# ADAPTER_WOLF.net
KiCad netlist of a schematic drawn in Altium Designer
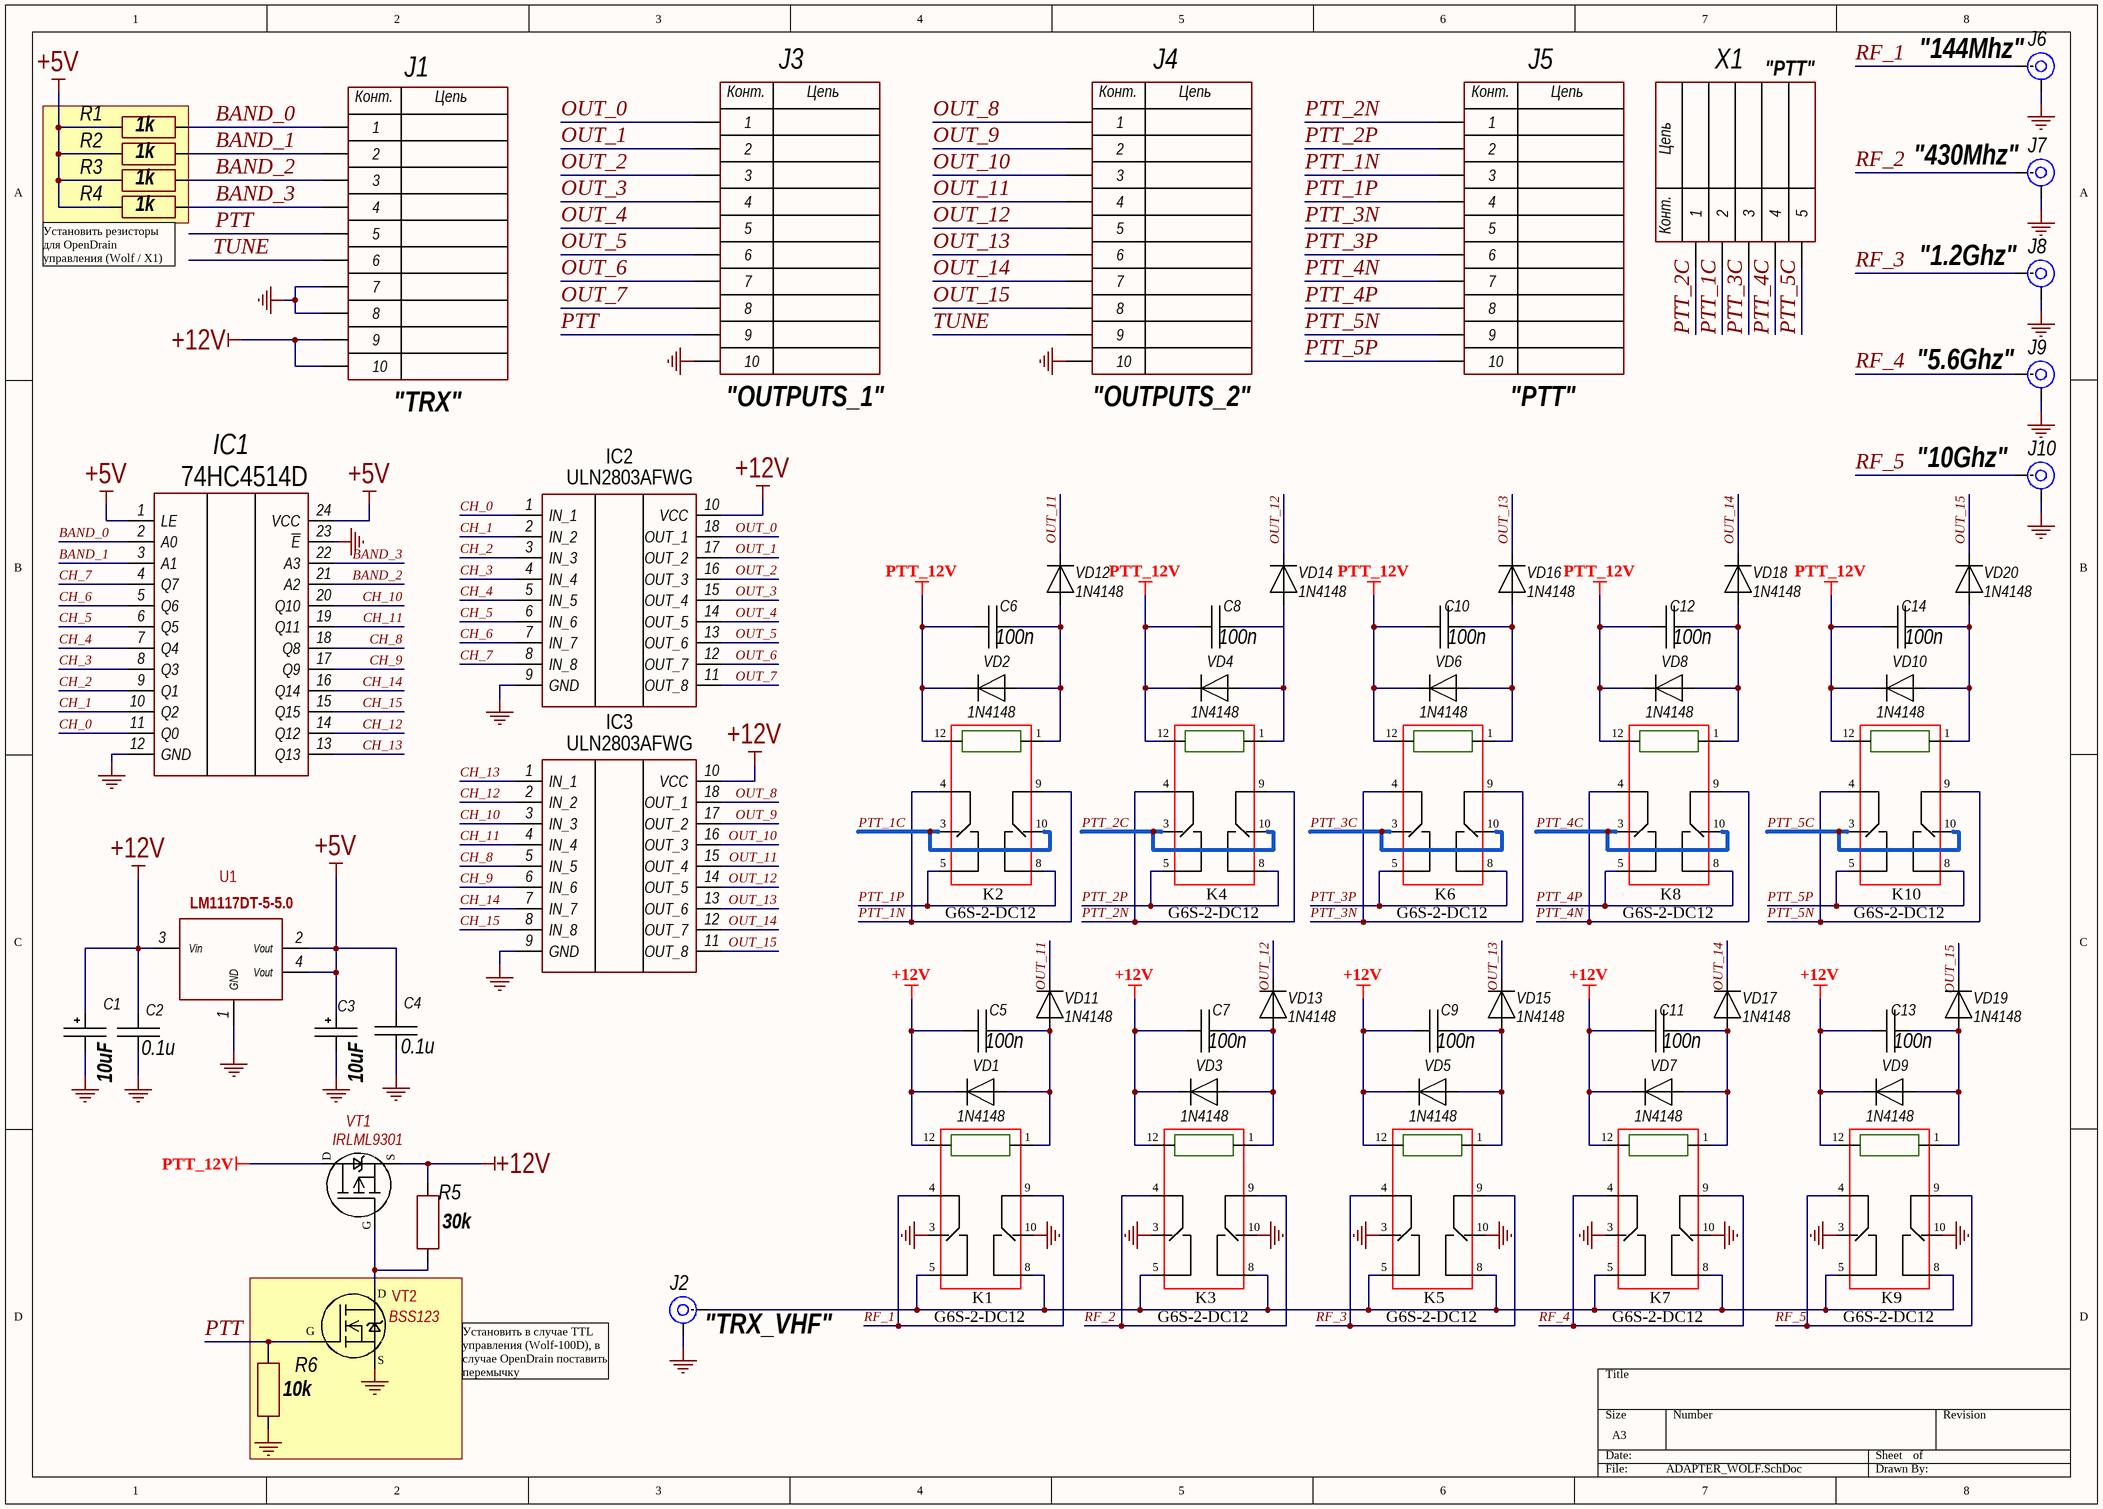
[diagram p0: ADAPTER_WOLF.SchDoc]

(export (version "E")
  (design (tool "Eeschema 10.0.6"))
  (components
    (comp (ref "C1")
      (value "10uF")
      (footprint "standard:TANTAL_B")
      (libsource (lib "Discrete") (part "TantalCap"))
    )
    (comp (ref "C2")
      (value "0.1u")
      (footprint "standard:CH0805C")
      (libsource (lib "Discrete") (part "Capacitor"))
    )
    (comp (ref "C3")
      (value "10uF")
      (footprint "standard:TANTAL_B")
      (libsource (lib "Discrete") (part "TantalCap"))
    )
    (comp (ref "C4")
      (value "0.1u")
      (footprint "standard:CH0805C")
      (libsource (lib "Discrete") (part "Capacitor"))
    )
    (comp (ref "C5")
      (value "100n")
      (footprint "standard:CH0805C")
      (libsource (lib "Discrete") (part "Capacitor"))
    )
    (comp (ref "C6")
      (value "100n")
      (footprint "standard:CH0805C")
      (libsource (lib "Discrete") (part "Capacitor"))
    )
    (comp (ref "C7")
      (value "100n")
      (footprint "standard:CH0805C")
      (libsource (lib "Discrete") (part "Capacitor"))
    )
    (comp (ref "C8")
      (value "100n")
      (footprint "standard:CH0805C")
      (libsource (lib "Discrete") (part "Capacitor"))
    )
    (comp (ref "C9")
      (value "100n")
      (footprint "standard:CH0805C")
      (libsource (lib "Discrete") (part "Capacitor"))
    )
    (comp (ref "C10")
      (value "100n")
      (footprint "standard:CH0805C")
      (libsource (lib "Discrete") (part "Capacitor"))
    )
    (comp (ref "C11")
      (value "100n")
      (footprint "standard:CH0805C")
      (libsource (lib "Discrete") (part "Capacitor"))
    )
    (comp (ref "C12")
      (value "100n")
      (footprint "standard:CH0805C")
      (libsource (lib "Discrete") (part "Capacitor"))
    )
    (comp (ref "C13")
      (value "100n")
      (footprint "standard:CH0805C")
      (libsource (lib "Discrete") (part "Capacitor"))
    )
    (comp (ref "C14")
      (value "100n")
      (footprint "standard:CH0805C")
      (libsource (lib "Discrete") (part "Capacitor"))
    )
    (comp (ref "IC1")
      (value "74HC4514D")
      (footprint "24-SOIC (W)")
      (libsource (lib "Digital") (part "74HC4514D"))
    )
    (comp (ref "IC2")
      (value "ULN2803AFWG")
      (footprint "18-SOIC (W)")
      (libsource (lib "Digital") (part "ULN2803AFWG"))
    )
    (comp (ref "IC3")
      (value "ULN2803AFWG")
      (footprint "18-SOIC (W)")
      (libsource (lib "Digital") (part "ULN2803AFWG"))
    )
    (comp (ref "J1")
      (value "\"TRX\"")
      (footprint "custom:CON: PLD-10")
      (libsource (lib "Connectors") (part "10-Connector"))
    )
    (comp (ref "J2")
      (value "\"TRX_VHF\"")
      (footprint "custom:CON: SMA")
      (description "RF")
      (libsource (lib "Connectors") (part "SMA"))
    )
    (comp (ref "J3")
      (value "\"OUTPUTS_1\"")
      (footprint "custom:CON: PLD-10")
      (libsource (lib "Connectors") (part "10-Connector"))
    )
    (comp (ref "J4")
      (value "\"OUTPUTS_2\"")
      (footprint "custom:CON: PLD-10")
      (libsource (lib "Connectors") (part "10-Connector"))
    )
    (comp (ref "J5")
      (value "\"PTT\"")
      (footprint "custom:CON: PLD-10")
      (libsource (lib "Connectors") (part "10-Connector"))
    )
    (comp (ref "J6")
      (value "\"144Mhz\"")
      (footprint "custom:CON: SMA")
      (description "RF")
      (libsource (lib "Connectors") (part "SMA"))
    )
    (comp (ref "J7")
      (value "\"430Mhz\"")
      (footprint "custom:CON: SMA")
      (description "RF")
      (libsource (lib "Connectors") (part "SMA"))
    )
    (comp (ref "J8")
      (value "\"1.2Ghz\"")
      (footprint "custom:CON: SMA")
      (description "RF")
      (libsource (lib "Connectors") (part "SMA"))
    )
    (comp (ref "J9")
      (value "\"5.6Ghz\"")
      (footprint "custom:CON: SMA")
      (description "RF")
      (libsource (lib "Connectors") (part "SMA"))
    )
    (comp (ref "J10")
      (value "\"10Ghz\"")
      (footprint "custom:CON: SMA")
      (description "RF")
      (libsource (lib "Connectors") (part "SMA"))
    )
    (comp (ref "K1")
      (value "G6S-2-DС12")
      (footprint "G6S-2-DC12")
      (libsource (lib "Relay") (part "G6S-2_TRS"))
    )
    (comp (ref "K2")
      (value "G6S-2-DС12")
      (footprint "G6S-2-DC12")
      (libsource (lib "Relay") (part "G6S-2_TRS"))
    )
    (comp (ref "K3")
      (value "G6S-2-DС12")
      (footprint "G6S-2-DC12")
      (libsource (lib "Relay") (part "G6S-2_TRS"))
    )
    (comp (ref "K4")
      (value "G6S-2-DС12")
      (footprint "G6S-2-DC12")
      (libsource (lib "Relay") (part "G6S-2_TRS"))
    )
    (comp (ref "K5") (value "G6S-2-DС12") (footprint "G6S-2-DC12") (libsource (lib "") (part "G6S-2_TRS_1")))
    (comp (ref "K6") (value "G6S-2-DС12") (footprint "G6S-2-DC12") (libsource (lib "") (part "G6S-2_TRS_2")))
    (comp (ref "K7")
      (value "G6S-2-DС12")
      (footprint "G6S-2-DC12")
      (libsource (lib "Relay") (part "G6S-2_TRS"))
    )
    (comp (ref "K8")
      (value "G6S-2-DС12")
      (footprint "G6S-2-DC12")
      (libsource (lib "Relay") (part "G6S-2_TRS"))
    )
    (comp (ref "K9")
      (value "G6S-2-DС12")
      (footprint "G6S-2-DC12")
      (libsource (lib "Relay") (part "G6S-2_TRS"))
    )
    (comp (ref "K10")
      (value "G6S-2-DС12")
      (footprint "G6S-2-DC12")
      (libsource (lib "Relay") (part "G6S-2_TRS"))
    )
    (comp (ref "R1")
      (value "1k")
      (footprint "standard:CH0805R")
      (libsource (lib "Discrete") (part "Resistor"))
    )
    (comp (ref "R2")
      (value "1k")
      (footprint "standard:CH0805R")
      (libsource (lib "Discrete") (part "Resistor"))
    )
    (comp (ref "R3") (value "1k") (footprint "standard:CH0805R") (libsource (lib "") (part "Resistor_2")))
    (comp (ref "R4")
      (value "1k")
      (footprint "standard:CH0805R")
      (libsource (lib "Discrete") (part "Resistor"))
    )
    (comp (ref "R5") (value "30k") (footprint "standard:CH0805R") (libsource (lib "") (part "Resistor_1")))
    (comp (ref "R6") (value "10k") (footprint "standard:CH0805R") (libsource (lib "") (part "Resistor_1")))
    (comp (ref "U1") (value "LM1117DT-5-5.0") (footprint "SOT223") (libsource (lib "Analog") (part "AMS117")))
    (comp (ref "VD1") (value "1N4148") (footprint "1N4148") (libsource (lib "Diods") (part "Diod")))
    (comp (ref "VD2") (value "1N4148") (footprint "1N4148") (libsource (lib "Diods") (part "Diod")))
    (comp (ref "VD3") (value "1N4148") (footprint "1N4148") (libsource (lib "Diods") (part "Diod")))
    (comp (ref "VD4") (value "1N4148") (footprint "1N4148") (libsource (lib "Diods") (part "Diod")))
    (comp (ref "VD5") (value "1N4148") (footprint "1N4148") (libsource (lib "Diods") (part "Diod")))
    (comp (ref "VD6") (value "1N4148") (footprint "1N4148") (libsource (lib "Diods") (part "Diod")))
    (comp (ref "VD7") (value "1N4148") (footprint "1N4148") (libsource (lib "Diods") (part "Diod")))
    (comp (ref "VD8") (value "1N4148") (footprint "1N4148") (libsource (lib "Diods") (part "Diod")))
    (comp (ref "VD9") (value "1N4148") (footprint "1N4148") (libsource (lib "Diods") (part "Diod")))
    (comp (ref "VD10") (value "1N4148") (footprint "1N4148") (libsource (lib "Diods") (part "Diod")))
    (comp (ref "VD11") (value "1N4148") (footprint "1N4148") (libsource (lib "Diods") (part "Diod")))
    (comp (ref "VD12") (value "1N4148") (footprint "1N4148") (libsource (lib "Diods") (part "Diod")))
    (comp (ref "VD13") (value "1N4148") (footprint "1N4148") (libsource (lib "Diods") (part "Diod")))
    (comp (ref "VD14") (value "1N4148") (footprint "1N4148") (libsource (lib "Diods") (part "Diod")))
    (comp (ref "VD15") (value "1N4148") (footprint "1N4148") (libsource (lib "Diods") (part "Diod")))
    (comp (ref "VD16") (value "1N4148") (footprint "1N4148") (libsource (lib "Diods") (part "Diod")))
    (comp (ref "VD17") (value "1N4148") (footprint "1N4148") (libsource (lib "Diods") (part "Diod")))
    (comp (ref "VD18") (value "1N4148") (footprint "1N4148") (libsource (lib "Diods") (part "Diod")))
    (comp (ref "VD19") (value "1N4148") (footprint "1N4148") (libsource (lib "Diods") (part "Diod")))
    (comp (ref "VD20") (value "1N4148") (footprint "1N4148") (libsource (lib "Diods") (part "Diod")))
    (comp (ref "VT1")
      (value "IRLML9301")
      (footprint "SOT23_132")
      (libsource (lib "Transistor") (part "P-KANAL"))
    )
    (comp (ref "VT2")
      (value "BSS123")
      (footprint "SOT23_132")
      (libsource (lib "Transistor") (part "N-KANAL"))
    )
    (comp (ref "X1")
      (value "\"PTT\"")
      (footprint "custom:CON: PLS-5")
      (libsource (lib "Connectors") (part "5-Connector"))
    )
  )
  (nets
    (net (code "1") (name "+5V") (class "Default")
      (node (ref "C3") (pin "1") (pinfunction "1_1") (pintype "power_in"))
      (node (ref "C4") (pin "2") (pinfunction "2_2") (pintype "power_in"))
      (node (ref "IC1") (pin "1") (pinfunction "LE_1") (pintype "passive"))
      (node (ref "IC1") (pin "24") (pinfunction "VCC_24") (pintype "passive"))
      (node (ref "R1") (pin "1") (pinfunction "1_1") (pintype "passive"))
      (node (ref "R2") (pin "1") (pinfunction "1_1") (pintype "passive"))
      (node (ref "R3") (pin "1") (pinfunction "1_1") (pintype "passive"))
      (node (ref "R4") (pin "1") (pinfunction "1_1") (pintype "passive"))
      (node (ref "U1") (pin "2") (pinfunction "Vout_2") (pintype "passive"))
      (node (ref "U1") (pin "4") (pinfunction "Vout_4") (pintype "passive"))
    )
    (net (code "2") (name "+12V") (class "Default")
      (node (ref "C1") (pin "1") (pinfunction "1_1") (pintype "power_in"))
      (node (ref "C11") (pin "1") (pinfunction "1_1") (pintype "power_in"))
      (node (ref "C13") (pin "1") (pinfunction "1_1") (pintype "power_in"))
      (node (ref "C2") (pin "2") (pinfunction "2_2") (pintype "power_in"))
      (node (ref "C5") (pin "1") (pinfunction "1_1") (pintype "power_in"))
      (node (ref "C7") (pin "1") (pinfunction "1_1") (pintype "power_in"))
      (node (ref "C9") (pin "1") (pinfunction "1_1") (pintype "power_in"))
      (node (ref "IC2") (pin "10") (pinfunction "VCC_10") (pintype "passive"))
      (node (ref "IC3") (pin "10") (pinfunction "VCC_10") (pintype "passive"))
      (node (ref "J1") (pin "10") (pinfunction "10_10") (pintype "power_in"))
      (node (ref "J1") (pin "9") (pinfunction "9_9") (pintype "power_in"))
      (node (ref "K1") (pin "12") (pinfunction "12_12") (pintype "passive"))
      (node (ref "K3") (pin "12") (pinfunction "12_12") (pintype "passive"))
      (node (ref "K5") (pin "12") (pinfunction "2_12") (pintype "passive"))
      (node (ref "K7") (pin "12") (pinfunction "12_12") (pintype "passive"))
      (node (ref "K9") (pin "12") (pinfunction "12_12") (pintype "passive"))
      (node (ref "R5") (pin "2") (pinfunction "2_2") (pintype "passive"))
      (node (ref "U1") (pin "3") (pinfunction "Vin_3") (pintype "passive"))
      (node (ref "VD1") (pin "2") (pinfunction "2_2") (pintype "passive"))
      (node (ref "VD3") (pin "2") (pinfunction "2_2") (pintype "passive"))
      (node (ref "VD5") (pin "2") (pinfunction "2_2") (pintype "passive"))
      (node (ref "VD7") (pin "2") (pinfunction "2_2") (pintype "passive"))
      (node (ref "VD9") (pin "2") (pinfunction "2_2") (pintype "passive"))
      (node (ref "VT1") (pin "2") (pinfunction "Исток_2") (pintype "passive"))
    )
    (net (code "3") (name "/BAND_0") (class "Default")
      (node (ref "IC1") (pin "2") (pinfunction "A0_2") (pintype "passive"))
      (node (ref "J1") (pin "1") (pinfunction "1_1") (pintype "passive"))
      (node (ref "R1") (pin "2") (pinfunction "2_2") (pintype "passive"))
    )
    (net (code "4") (name "/BAND_1") (class "Default")
      (node (ref "IC1") (pin "3") (pinfunction "A1_3") (pintype "passive"))
      (node (ref "J1") (pin "2") (pinfunction "2_2") (pintype "passive"))
      (node (ref "R2") (pin "2") (pinfunction "2_2") (pintype "passive"))
    )
    (net (code "5") (name "/BAND_2") (class "Default")
      (node (ref "IC1") (pin "21") (pinfunction "A2_21") (pintype "passive"))
      (node (ref "J1") (pin "3") (pinfunction "3_3") (pintype "power_in"))
      (node (ref "R3") (pin "2") (pinfunction "2_2") (pintype "passive"))
    )
    (net (code "6") (name "/BAND_3") (class "Default")
      (node (ref "IC1") (pin "22") (pinfunction "A3_22") (pintype "passive"))
      (node (ref "J1") (pin "4") (pinfunction "4_4") (pintype "power_in"))
      (node (ref "R4") (pin "2") (pinfunction "2_2") (pintype "passive"))
    )
    (net (code "7") (name "/CH_0") (class "Default")
      (node (ref "IC1") (pin "11") (pinfunction "Q0_11") (pintype "passive"))
      (node (ref "IC2") (pin "1") (pinfunction "IN_1_1") (pintype "passive"))
    )
    (net (code "8") (name "/CH_1") (class "Default")
      (node (ref "IC1") (pin "10") (pinfunction "Q2_10") (pintype "passive"))
      (node (ref "IC2") (pin "2") (pinfunction "IN_2_2") (pintype "passive"))
    )
    (net (code "9") (name "/CH_2") (class "Default")
      (node (ref "IC1") (pin "9") (pinfunction "Q1_9") (pintype "passive"))
      (node (ref "IC2") (pin "3") (pinfunction "IN_3_3") (pintype "passive"))
    )
    (net (code "10") (name "/CH_3") (class "Default")
      (node (ref "IC1") (pin "8") (pinfunction "Q3_8") (pintype "passive"))
      (node (ref "IC2") (pin "4") (pinfunction "IN_4_4") (pintype "passive"))
    )
    (net (code "11") (name "/CH_4") (class "Default")
      (node (ref "IC1") (pin "7") (pinfunction "Q4_7") (pintype "passive"))
      (node (ref "IC2") (pin "5") (pinfunction "IN_5_5") (pintype "passive"))
    )
    (net (code "12") (name "/CH_5") (class "Default")
      (node (ref "IC1") (pin "6") (pinfunction "Q5_6") (pintype "passive"))
      (node (ref "IC2") (pin "6") (pinfunction "IN_6_6") (pintype "passive"))
    )
    (net (code "13") (name "/CH_6") (class "Default")
      (node (ref "IC1") (pin "5") (pinfunction "Q6_5") (pintype "passive"))
      (node (ref "IC2") (pin "7") (pinfunction "IN_7_7") (pintype "passive"))
    )
    (net (code "14") (name "/CH_7") (class "Default")
      (node (ref "IC1") (pin "4") (pinfunction "Q7_4") (pintype "passive"))
      (node (ref "IC2") (pin "8") (pinfunction "IN_8_8") (pintype "passive"))
    )
    (net (code "15") (name "/CH_8") (class "Default")
      (node (ref "IC1") (pin "18") (pinfunction "Q8_18") (pintype "passive"))
      (node (ref "IC3") (pin "5") (pinfunction "IN_5_5") (pintype "passive"))
    )
    (net (code "16") (name "/CH_9") (class "Default")
      (node (ref "IC1") (pin "17") (pinfunction "Q9_17") (pintype "passive"))
      (node (ref "IC3") (pin "6") (pinfunction "IN_6_6") (pintype "passive"))
    )
    (net (code "17") (name "/CH_10") (class "Default")
      (node (ref "IC1") (pin "20") (pinfunction "Q10_20") (pintype "passive"))
      (node (ref "IC3") (pin "3") (pinfunction "IN_3_3") (pintype "passive"))
    )
    (net (code "18") (name "/CH_11") (class "Default")
      (node (ref "IC1") (pin "19") (pinfunction "Q11_19") (pintype "passive"))
      (node (ref "IC3") (pin "4") (pinfunction "IN_4_4") (pintype "passive"))
    )
    (net (code "19") (name "/CH_12") (class "Default")
      (node (ref "IC1") (pin "14") (pinfunction "Q12_14") (pintype "passive"))
      (node (ref "IC3") (pin "2") (pinfunction "IN_2_2") (pintype "passive"))
    )
    (net (code "20") (name "/CH_13") (class "Default")
      (node (ref "IC1") (pin "13") (pinfunction "Q13_13") (pintype "passive"))
      (node (ref "IC3") (pin "1") (pinfunction "IN_1_1") (pintype "passive"))
    )
    (net (code "21") (name "/CH_14") (class "Default")
      (node (ref "IC1") (pin "16") (pinfunction "Q14_16") (pintype "passive"))
      (node (ref "IC3") (pin "7") (pinfunction "IN_7_7") (pintype "passive"))
    )
    (net (code "22") (name "/CH_15") (class "Default")
      (node (ref "IC1") (pin "15") (pinfunction "Q15_15") (pintype "passive"))
      (node (ref "IC3") (pin "8") (pinfunction "IN_8_8") (pintype "passive"))
    )
    (net (code "23") (name "/OUT_0") (class "Default")
      (node (ref "IC2") (pin "18") (pinfunction "OUT_1_18") (pintype "passive"))
      (node (ref "J3") (pin "1") (pinfunction "1_1") (pintype "passive"))
    )
    (net (code "24") (name "/OUT_1") (class "Default")
      (node (ref "IC2") (pin "17") (pinfunction "OUT_2_17") (pintype "passive"))
      (node (ref "J3") (pin "2") (pinfunction "2_2") (pintype "passive"))
    )
    (net (code "25") (name "/OUT_2") (class "Default")
      (node (ref "IC2") (pin "16") (pinfunction "OUT_3_16") (pintype "passive"))
      (node (ref "J3") (pin "3") (pinfunction "3_3") (pintype "power_in"))
    )
    (net (code "26") (name "/OUT_3") (class "Default")
      (node (ref "IC2") (pin "15") (pinfunction "OUT_4_15") (pintype "passive"))
      (node (ref "J3") (pin "4") (pinfunction "4_4") (pintype "power_in"))
    )
    (net (code "27") (name "/OUT_4") (class "Default")
      (node (ref "IC2") (pin "14") (pinfunction "OUT_5_14") (pintype "passive"))
      (node (ref "J3") (pin "5") (pinfunction "5_5") (pintype "power_in"))
    )
    (net (code "28") (name "/OUT_5") (class "Default")
      (node (ref "IC2") (pin "13") (pinfunction "OUT_6_13") (pintype "passive"))
      (node (ref "J3") (pin "6") (pinfunction "6_6") (pintype "power_in"))
    )
    (net (code "29") (name "/OUT_6") (class "Default")
      (node (ref "IC2") (pin "12") (pinfunction "OUT_7_12") (pintype "passive"))
      (node (ref "J3") (pin "7") (pinfunction "7_7") (pintype "power_in"))
    )
    (net (code "30") (name "/OUT_7") (class "Default")
      (node (ref "IC2") (pin "11") (pinfunction "OUT_8_11") (pintype "passive"))
      (node (ref "J3") (pin "8") (pinfunction "8_8") (pintype "power_in"))
    )
    (net (code "31") (name "/OUT_8") (class "Default")
      (node (ref "IC3") (pin "18") (pinfunction "OUT_1_18") (pintype "passive"))
      (node (ref "J4") (pin "1") (pinfunction "1_1") (pintype "passive"))
    )
    (net (code "32") (name "/OUT_9") (class "Default")
      (node (ref "IC3") (pin "17") (pinfunction "OUT_2_17") (pintype "passive"))
      (node (ref "J4") (pin "2") (pinfunction "2_2") (pintype "passive"))
    )
    (net (code "33") (name "/OUT_10") (class "Default")
      (node (ref "IC3") (pin "16") (pinfunction "OUT_3_16") (pintype "passive"))
      (node (ref "J4") (pin "3") (pinfunction "3_3") (pintype "power_in"))
    )
    (net (code "34") (name "/OUT_11") (class "Default")
      (node (ref "IC3") (pin "15") (pinfunction "OUT_4_15") (pintype "passive"))
      (node (ref "J4") (pin "4") (pinfunction "4_4") (pintype "power_in"))
      (node (ref "VD11") (pin "2") (pinfunction "2_2") (pintype "passive"))
      (node (ref "VD12") (pin "2") (pinfunction "2_2") (pintype "passive"))
    )
    (net (code "35") (name "/OUT_12") (class "Default")
      (node (ref "IC3") (pin "14") (pinfunction "OUT_5_14") (pintype "passive"))
      (node (ref "J4") (pin "5") (pinfunction "5_5") (pintype "power_in"))
      (node (ref "VD13") (pin "2") (pinfunction "2_2") (pintype "passive"))
      (node (ref "VD14") (pin "2") (pinfunction "2_2") (pintype "passive"))
    )
    (net (code "36") (name "/OUT_13") (class "Default")
      (node (ref "IC3") (pin "13") (pinfunction "OUT_6_13") (pintype "passive"))
      (node (ref "J4") (pin "6") (pinfunction "6_6") (pintype "power_in"))
      (node (ref "VD15") (pin "2") (pinfunction "2_2") (pintype "passive"))
      (node (ref "VD16") (pin "2") (pinfunction "2_2") (pintype "passive"))
    )
    (net (code "37") (name "/OUT_14") (class "Default")
      (node (ref "IC3") (pin "12") (pinfunction "OUT_7_12") (pintype "passive"))
      (node (ref "J4") (pin "7") (pinfunction "7_7") (pintype "power_in"))
      (node (ref "VD17") (pin "2") (pinfunction "2_2") (pintype "passive"))
      (node (ref "VD18") (pin "2") (pinfunction "2_2") (pintype "passive"))
    )
    (net (code "38") (name "/OUT_15") (class "Default")
      (node (ref "IC3") (pin "11") (pinfunction "OUT_8_11") (pintype "passive"))
      (node (ref "J4") (pin "8") (pinfunction "8_8") (pintype "power_in"))
      (node (ref "VD19") (pin "2") (pinfunction "2_2") (pintype "passive"))
      (node (ref "VD20") (pin "2") (pinfunction "2_2") (pintype "passive"))
    )
    (net (code "39") (name "/PTT") (class "Default")
      (node (ref "J1") (pin "5") (pinfunction "5_5") (pintype "power_in"))
      (node (ref "J3") (pin "9") (pinfunction "9_9") (pintype "power_in"))
      (node (ref "R6") (pin "2") (pinfunction "2_2") (pintype "passive"))
      (node (ref "VT2") (pin "1") (pinfunction "Затвор_1") (pintype "passive"))
    )
    (net (code "40") (name "/PTT_1N") (class "Default")
      (node (ref "J5") (pin "3") (pinfunction "3_3") (pintype "power_in"))
      (node (ref "K2") (pin "4") (pinfunction "4_4") (pintype "passive"))
      (node (ref "K2") (pin "9") (pinfunction "9_9") (pintype "passive"))
    )
    (net (code "41") (name "/PTT_1P") (class "Default")
      (node (ref "J5") (pin "4") (pinfunction "4_4") (pintype "power_in"))
      (node (ref "K2") (pin "5") (pinfunction "5_5") (pintype "passive"))
      (node (ref "K2") (pin "8") (pinfunction "8_8") (pintype "passive"))
    )
    (net (code "42") (name "/PTT_1С") (class "Default")
      (node (ref "K2") (pin "10") (pinfunction "10_10") (pintype "passive"))
      (node (ref "K2") (pin "3") (pinfunction "3_3") (pintype "passive"))
      (node (ref "X1") (pin "2") (pinfunction "2_2") (pintype "passive"))
    )
    (net (code "43") (name "/PTT_2N") (class "Default")
      (node (ref "J5") (pin "1") (pinfunction "1_1") (pintype "passive"))
      (node (ref "K4") (pin "4") (pinfunction "4_4") (pintype "passive"))
      (node (ref "K4") (pin "9") (pinfunction "9_9") (pintype "passive"))
    )
    (net (code "44") (name "/PTT_2P") (class "Default")
      (node (ref "J5") (pin "2") (pinfunction "2_2") (pintype "passive"))
      (node (ref "K4") (pin "5") (pinfunction "5_5") (pintype "passive"))
      (node (ref "K4") (pin "8") (pinfunction "8_8") (pintype "passive"))
    )
    (net (code "45") (name "/PTT_2С") (class "Default")
      (node (ref "K4") (pin "10") (pinfunction "10_10") (pintype "passive"))
      (node (ref "K4") (pin "3") (pinfunction "3_3") (pintype "passive"))
      (node (ref "X1") (pin "1") (pinfunction "1_1") (pintype "passive"))
    )
    (net (code "46") (name "/PTT_3N") (class "Default")
      (node (ref "J5") (pin "5") (pinfunction "5_5") (pintype "power_in"))
      (node (ref "K6") (pin "4") (pinfunction "4_4") (pintype "passive"))
      (node (ref "K6") (pin "9") (pinfunction "9_9") (pintype "passive"))
    )
    (net (code "47") (name "/PTT_3P") (class "Default")
      (node (ref "J5") (pin "6") (pinfunction "6_6") (pintype "power_in"))
      (node (ref "K6") (pin "5") (pinfunction "5_5") (pintype "passive"))
      (node (ref "K6") (pin "8") (pinfunction "8_8") (pintype "passive"))
    )
    (net (code "48") (name "/PTT_3С") (class "Default")
      (node (ref "K6") (pin "10") (pinfunction "10_10") (pintype "passive"))
      (node (ref "K6") (pin "3") (pinfunction "3_3") (pintype "passive"))
      (node (ref "X1") (pin "3") (pinfunction "3_3") (pintype "power_in"))
    )
    (net (code "49") (name "/PTT_4N") (class "Default")
      (node (ref "J5") (pin "7") (pinfunction "7_7") (pintype "power_in"))
      (node (ref "K8") (pin "4") (pinfunction "4_4") (pintype "passive"))
      (node (ref "K8") (pin "9") (pinfunction "9_9") (pintype "passive"))
    )
    (net (code "50") (name "/PTT_4P") (class "Default")
      (node (ref "J5") (pin "8") (pinfunction "8_8") (pintype "power_in"))
      (node (ref "K8") (pin "5") (pinfunction "5_5") (pintype "passive"))
      (node (ref "K8") (pin "8") (pinfunction "8_8") (pintype "passive"))
    )
    (net (code "51") (name "/PTT_4С") (class "Default")
      (node (ref "K8") (pin "10") (pinfunction "10_10") (pintype "passive"))
      (node (ref "K8") (pin "3") (pinfunction "3_3") (pintype "passive"))
      (node (ref "X1") (pin "4") (pinfunction "4_4") (pintype "power_in"))
    )
    (net (code "52") (name "/PTT_5N") (class "Default")
      (node (ref "J5") (pin "9") (pinfunction "9_9") (pintype "power_in"))
      (node (ref "K10") (pin "4") (pinfunction "4_4") (pintype "passive"))
      (node (ref "K10") (pin "9") (pinfunction "9_9") (pintype "passive"))
    )
    (net (code "53") (name "/PTT_5P") (class "Default")
      (node (ref "J5") (pin "10") (pinfunction "10_10") (pintype "power_in"))
      (node (ref "K10") (pin "5") (pinfunction "5_5") (pintype "passive"))
      (node (ref "K10") (pin "8") (pinfunction "8_8") (pintype "passive"))
    )
    (net (code "54") (name "/PTT_5С") (class "Default")
      (node (ref "K10") (pin "10") (pinfunction "10_10") (pintype "passive"))
      (node (ref "K10") (pin "3") (pinfunction "3_3") (pintype "passive"))
      (node (ref "X1") (pin "5") (pinfunction "5_5") (pintype "power_in"))
    )
    (net (code "55") (name "/RF_1") (class "Default")
      (node (ref "J6") (pin "1") (pinfunction "IN_1") (pintype "passive"))
      (node (ref "K1") (pin "4") (pinfunction "4_4") (pintype "passive"))
      (node (ref "K1") (pin "9") (pinfunction "9_9") (pintype "passive"))
    )
    (net (code "56") (name "/RF_2") (class "Default")
      (node (ref "J7") (pin "1") (pinfunction "IN_1") (pintype "passive"))
      (node (ref "K3") (pin "4") (pinfunction "4_4") (pintype "passive"))
      (node (ref "K3") (pin "9") (pinfunction "9_9") (pintype "passive"))
    )
    (net (code "57") (name "/RF_3") (class "Default")
      (node (ref "J8") (pin "1") (pinfunction "IN_1") (pintype "passive"))
      (node (ref "K5") (pin "4") (pinfunction "4_4") (pintype "passive"))
      (node (ref "K5") (pin "9") (pinfunction "9_9") (pintype "passive"))
    )
    (net (code "58") (name "/RF_4") (class "Default")
      (node (ref "J9") (pin "1") (pinfunction "IN_1") (pintype "passive"))
      (node (ref "K7") (pin "4") (pinfunction "4_4") (pintype "passive"))
      (node (ref "K7") (pin "9") (pinfunction "9_9") (pintype "passive"))
    )
    (net (code "59") (name "/RF_5") (class "Default")
      (node (ref "J10") (pin "1") (pinfunction "IN_1") (pintype "passive"))
      (node (ref "K9") (pin "4") (pinfunction "4_4") (pintype "passive"))
      (node (ref "K9") (pin "9") (pinfunction "9_9") (pintype "passive"))
    )
    (net (code "60") (name "/TUNE") (class "Default")
      (node (ref "J1") (pin "6") (pinfunction "6_6") (pintype "power_in"))
      (node (ref "J4") (pin "9") (pinfunction "9_9") (pintype "power_in"))
    )
    (net (code "61") (name "GND") (class "Default")
      (node (ref "C1") (pin "2") (pinfunction "2_2") (pintype "power_in"))
      (node (ref "C2") (pin "1") (pinfunction "1_1") (pintype "power_in"))
      (node (ref "C3") (pin "2") (pinfunction "2_2") (pintype "power_in"))
      (node (ref "C4") (pin "1") (pinfunction "1_1") (pintype "power_in"))
      (node (ref "IC1") (pin "12") (pinfunction "GND_12") (pintype "passive"))
      (node (ref "IC1") (pin "23") (pinfunction "~{E}_23") (pintype "passive"))
      (node (ref "IC2") (pin "9") (pinfunction "GND_9") (pintype "passive"))
      (node (ref "IC3") (pin "9") (pinfunction "GND_9") (pintype "passive"))
      (node (ref "J1") (pin "7") (pinfunction "7_7") (pintype "power_in"))
      (node (ref "J1") (pin "8") (pinfunction "8_8") (pintype "power_in"))
      (node (ref "J10") (pin "2") (pinfunction "IN_2") (pintype "passive"))
      (node (ref "J2") (pin "2") (pinfunction "IN_2") (pintype "passive"))
      (node (ref "J3") (pin "10") (pinfunction "10_10") (pintype "power_in"))
      (node (ref "J4") (pin "10") (pinfunction "10_10") (pintype "power_in"))
      (node (ref "J6") (pin "2") (pinfunction "IN_2") (pintype "passive"))
      (node (ref "J7") (pin "2") (pinfunction "IN_2") (pintype "passive"))
      (node (ref "J8") (pin "2") (pinfunction "IN_2") (pintype "passive"))
      (node (ref "J9") (pin "2") (pinfunction "IN_2") (pintype "passive"))
      (node (ref "K1") (pin "10") (pinfunction "10_10") (pintype "passive"))
      (node (ref "K1") (pin "3") (pinfunction "3_3") (pintype "passive"))
      (node (ref "K3") (pin "10") (pinfunction "10_10") (pintype "passive"))
      (node (ref "K3") (pin "3") (pinfunction "3_3") (pintype "passive"))
      (node (ref "K5") (pin "10") (pinfunction "10_10") (pintype "passive"))
      (node (ref "K5") (pin "3") (pinfunction "3_3") (pintype "passive"))
      (node (ref "K7") (pin "10") (pinfunction "10_10") (pintype "passive"))
      (node (ref "K7") (pin "3") (pinfunction "3_3") (pintype "passive"))
      (node (ref "K9") (pin "10") (pinfunction "10_10") (pintype "passive"))
      (node (ref "K9") (pin "3") (pinfunction "3_3") (pintype "passive"))
      (node (ref "R6") (pin "1") (pinfunction "1_1") (pintype "passive"))
      (node (ref "U1") (pin "1") (pinfunction "GND_1") (pintype "passive"))
      (node (ref "VT2") (pin "2") (pinfunction "Исток_2") (pintype "passive"))
    )
    (net (code "62") (name "Net-(C5-Pad2)") (class "Default")
      (node (ref "C5") (pin "2") (pinfunction "2_2") (pintype "power_in"))
      (node (ref "K1") (pin "1") (pinfunction "1_1") (pintype "passive"))
      (node (ref "VD1") (pin "1") (pinfunction "1_1") (pintype "passive"))
      (node (ref "VD11") (pin "1") (pinfunction "1_1") (pintype "passive"))
    )
    (net (code "63") (name "Net-(C6-Pad2)") (class "Default")
      (node (ref "C6") (pin "2") (pinfunction "2_2") (pintype "power_in"))
      (node (ref "K2") (pin "1") (pinfunction "1_1") (pintype "passive"))
      (node (ref "VD12") (pin "1") (pinfunction "1_1") (pintype "passive"))
      (node (ref "VD2") (pin "1") (pinfunction "1_1") (pintype "passive"))
    )
    (net (code "64") (name "Net-(C7-Pad2)") (class "Default")
      (node (ref "C7") (pin "2") (pinfunction "2_2") (pintype "power_in"))
      (node (ref "K3") (pin "1") (pinfunction "1_1") (pintype "passive"))
      (node (ref "VD13") (pin "1") (pinfunction "1_1") (pintype "passive"))
      (node (ref "VD3") (pin "1") (pinfunction "1_1") (pintype "passive"))
    )
    (net (code "65") (name "Net-(C8-Pad2)") (class "Default")
      (node (ref "C8") (pin "2") (pinfunction "2_2") (pintype "power_in"))
      (node (ref "K4") (pin "1") (pinfunction "1_1") (pintype "passive"))
      (node (ref "VD14") (pin "1") (pinfunction "1_1") (pintype "passive"))
      (node (ref "VD4") (pin "1") (pinfunction "1_1") (pintype "passive"))
    )
    (net (code "66") (name "Net-(C9-Pad2)") (class "Default")
      (node (ref "C9") (pin "2") (pinfunction "2_2") (pintype "power_in"))
      (node (ref "K5") (pin "1") (pinfunction "1_1") (pintype "passive"))
      (node (ref "VD15") (pin "1") (pinfunction "1_1") (pintype "passive"))
      (node (ref "VD5") (pin "1") (pinfunction "1_1") (pintype "passive"))
    )
    (net (code "67") (name "Net-(C10-Pad2)") (class "Default")
      (node (ref "C10") (pin "2") (pinfunction "2_2") (pintype "power_in"))
      (node (ref "K6") (pin "1") (pinfunction "1_1") (pintype "passive"))
      (node (ref "VD16") (pin "1") (pinfunction "1_1") (pintype "passive"))
      (node (ref "VD6") (pin "1") (pinfunction "1_1") (pintype "passive"))
    )
    (net (code "68") (name "Net-(C11-Pad2)") (class "Default")
      (node (ref "C11") (pin "2") (pinfunction "2_2") (pintype "power_in"))
      (node (ref "K7") (pin "1") (pinfunction "1_1") (pintype "passive"))
      (node (ref "VD17") (pin "1") (pinfunction "1_1") (pintype "passive"))
      (node (ref "VD7") (pin "1") (pinfunction "1_1") (pintype "passive"))
    )
    (net (code "69") (name "Net-(C12-Pad2)") (class "Default")
      (node (ref "C12") (pin "2") (pinfunction "2_2") (pintype "power_in"))
      (node (ref "K8") (pin "1") (pinfunction "1_1") (pintype "passive"))
      (node (ref "VD18") (pin "1") (pinfunction "1_1") (pintype "passive"))
      (node (ref "VD8") (pin "1") (pinfunction "1_1") (pintype "passive"))
    )
    (net (code "70") (name "Net-(C13-Pad2)") (class "Default")
      (node (ref "C13") (pin "2") (pinfunction "2_2") (pintype "power_in"))
      (node (ref "K9") (pin "1") (pinfunction "1_1") (pintype "passive"))
      (node (ref "VD19") (pin "1") (pinfunction "1_1") (pintype "passive"))
      (node (ref "VD9") (pin "1") (pinfunction "1_1") (pintype "passive"))
    )
    (net (code "71") (name "Net-(C14-Pad2)") (class "Default")
      (node (ref "C14") (pin "2") (pinfunction "2_2") (pintype "power_in"))
      (node (ref "K10") (pin "1") (pinfunction "1_1") (pintype "passive"))
      (node (ref "VD10") (pin "1") (pinfunction "1_1") (pintype "passive"))
      (node (ref "VD20") (pin "1") (pinfunction "1_1") (pintype "passive"))
    )
    (net (code "72") (name "Net-(J2-IN-Pad1)") (class "Default")
      (node (ref "J2") (pin "1") (pinfunction "IN_1") (pintype "passive"))
      (node (ref "K1") (pin "5") (pinfunction "5_5") (pintype "passive"))
      (node (ref "K1") (pin "8") (pinfunction "8_8") (pintype "passive"))
      (node (ref "K3") (pin "5") (pinfunction "5_5") (pintype "passive"))
      (node (ref "K3") (pin "8") (pinfunction "8_8") (pintype "passive"))
      (node (ref "K5") (pin "5") (pinfunction "5_5") (pintype "passive"))
      (node (ref "K5") (pin "8") (pinfunction "8_8") (pintype "passive"))
      (node (ref "K7") (pin "5") (pinfunction "5_5") (pintype "passive"))
      (node (ref "K7") (pin "8") (pinfunction "8_8") (pintype "passive"))
      (node (ref "K9") (pin "5") (pinfunction "5_5") (pintype "passive"))
      (node (ref "K9") (pin "8") (pinfunction "8_8") (pintype "passive"))
    )
    (net (code "73") (name "Net-(VT1-Затвор(Gate))") (class "Default")
      (node (ref "R5") (pin "1") (pinfunction "1_1") (pintype "passive"))
      (node (ref "VT1") (pin "1") (pinfunction "Затвор(Gate)_1") (pintype "passive"))
      (node (ref "VT2") (pin "3") (pinfunction "Сток_3") (pintype "passive"))
    )
    (net (code "74") (name "PTT_12V") (class "Default")
      (node (ref "C10") (pin "1") (pinfunction "1_1") (pintype "power_in"))
      (node (ref "C12") (pin "1") (pinfunction "1_1") (pintype "power_in"))
      (node (ref "C14") (pin "1") (pinfunction "1_1") (pintype "power_in"))
      (node (ref "C6") (pin "1") (pinfunction "1_1") (pintype "power_in"))
      (node (ref "C8") (pin "1") (pinfunction "1_1") (pintype "power_in"))
      (node (ref "K10") (pin "12") (pinfunction "12_12") (pintype "passive"))
      (node (ref "K2") (pin "12") (pinfunction "12_12") (pintype "passive"))
      (node (ref "K4") (pin "12") (pinfunction "12_12") (pintype "passive"))
      (node (ref "K6") (pin "12") (pinfunction "12_12") (pintype "passive"))
      (node (ref "K8") (pin "12") (pinfunction "12_12") (pintype "passive"))
      (node (ref "VD10") (pin "2") (pinfunction "2_2") (pintype "passive"))
      (node (ref "VD2") (pin "2") (pinfunction "2_2") (pintype "passive"))
      (node (ref "VD4") (pin "2") (pinfunction "2_2") (pintype "passive"))
      (node (ref "VD6") (pin "2") (pinfunction "2_2") (pintype "passive"))
      (node (ref "VD8") (pin "2") (pinfunction "2_2") (pintype "passive"))
      (node (ref "VT1") (pin "3") (pinfunction "Сток_3") (pintype "passive"))
    )
  )
)
